# encoder.net
KiCad netlist of a schematic drawn in EAGLE
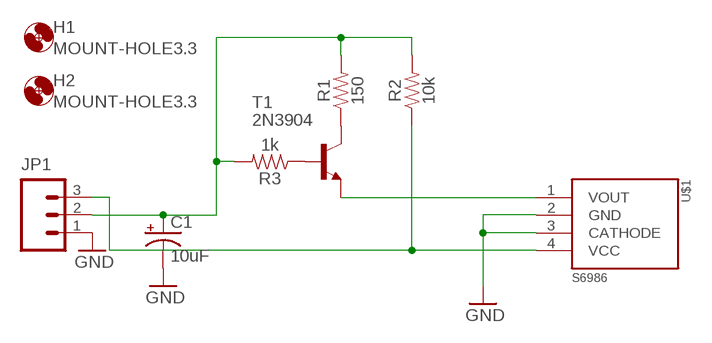
[diagram p0: schematic, sheet 1]

(export (version "E")
  (design (tool "Eeschema 10.0.6"))
  (components
    (comp (ref "C1")
      (value "10uF")
      (footprint "eagle-import:CPOL-RADIAL-2.5MM-5MM-KIT")
      (libsource (lib "eagle-import") (part "10UF-POLAR-RADIAL-2.5MM-KIT-25V-20%"))
    )
    (comp (ref "H1")
      (value "MOUNT-HOLE3.3")
      (footprint "eagle-import:3,3")
      (libsource (lib "eagle-import") (part "MOUNT-HOLE3.3"))
    )
    (comp (ref "H2")
      (value "MOUNT-HOLE3.3")
      (footprint "eagle-import:3,3")
      (libsource (lib "eagle-import") (part "MOUNT-HOLE3.3"))
    )
    (comp (ref "JP1")
      (value "M03PTH")
      (footprint "eagle-import:1X03")
      (libsource (lib "eagle-import") (part "M03PTH"))
    )
    (comp (ref "R1")
      (value "150")
      (footprint "eagle-import:AXIAL-0.3")
      (libsource (lib "eagle-import") (part "10OHM-HORIZ-1/4W-1%"))
    )
    (comp (ref "R2")
      (value "10k")
      (footprint "eagle-import:AXIAL-0.3")
      (libsource (lib "eagle-import") (part "10OHM-HORIZ-1/4W-1%"))
    )
    (comp (ref "R3")
      (value "1k")
      (footprint "eagle-import:AXIAL-0.3")
      (libsource (lib "eagle-import") (part "10OHM-HORIZ-1/4W-1%"))
    )
    (comp (ref "T1")
      (value "2N3904")
      (footprint "eagle-import:TO92")
      (libsource (lib "eagle-import") (part "2N3904"))
    )
    (comp (ref "U$1")
      (value "S6986")
      (footprint "eagle-import:S6986")
      (libsource (lib "eagle-import") (part "S6986"))
    )
  )
  (nets
    (net (code "1") (name "GND") (class "Default")
      (node (ref "C1") (pin "2") (pinfunction "-_2") (pintype "passive"))
      (node (ref "JP1") (pin "1") (pinfunction "1_1") (pintype "passive"))
      (node (ref "U$1") (pin "2") (pinfunction "GND_2") (pintype "bidirectional"))
      (node (ref "U$1") (pin "3") (pinfunction "CATHODE_3") (pintype "bidirectional"))
    )
    (net (code "2") (name "Net-(C1-+)") (class "Default")
      (node (ref "C1") (pin "1") (pinfunction "+_1") (pintype "passive"))
      (node (ref "JP1") (pin "2") (pinfunction "2_2") (pintype "passive"))
      (node (ref "R1") (pin "P$2") (pinfunction "2_P$2") (pintype "passive"))
      (node (ref "R2") (pin "P$2") (pinfunction "2_P$2") (pintype "passive"))
      (node (ref "R3") (pin "P$2") (pinfunction "2_P$2") (pintype "passive"))
    )
    (net (code "3") (name "Net-(R1-1)") (class "Default")
      (node (ref "R1") (pin "P$1") (pinfunction "1_P$1") (pintype "passive"))
      (node (ref "T1") (pin "1") (pinfunction "C_1") (pintype "passive"))
    )
    (net (code "4") (name "Net-(R2-1)") (class "Default")
      (node (ref "JP1") (pin "3") (pinfunction "3_3") (pintype "passive"))
      (node (ref "R2") (pin "P$1") (pinfunction "1_P$1") (pintype "passive"))
      (node (ref "U$1") (pin "4") (pinfunction "VCC_4") (pintype "bidirectional"))
    )
    (net (code "5") (name "Net-(R3-1)") (class "Default")
      (node (ref "R3") (pin "P$1") (pinfunction "1_P$1") (pintype "passive"))
      (node (ref "T1") (pin "2") (pinfunction "B_2") (pintype "passive"))
    )
    (net (code "6") (name "Net-(T1-E)") (class "Default")
      (node (ref "T1") (pin "3") (pinfunction "E_3") (pintype "passive"))
      (node (ref "U$1") (pin "1") (pinfunction "VOUT_1") (pintype "bidirectional"))
    )
  )
)
